# PAGE2.net
KiCad netlist of a schematic drawn in Altium Designer
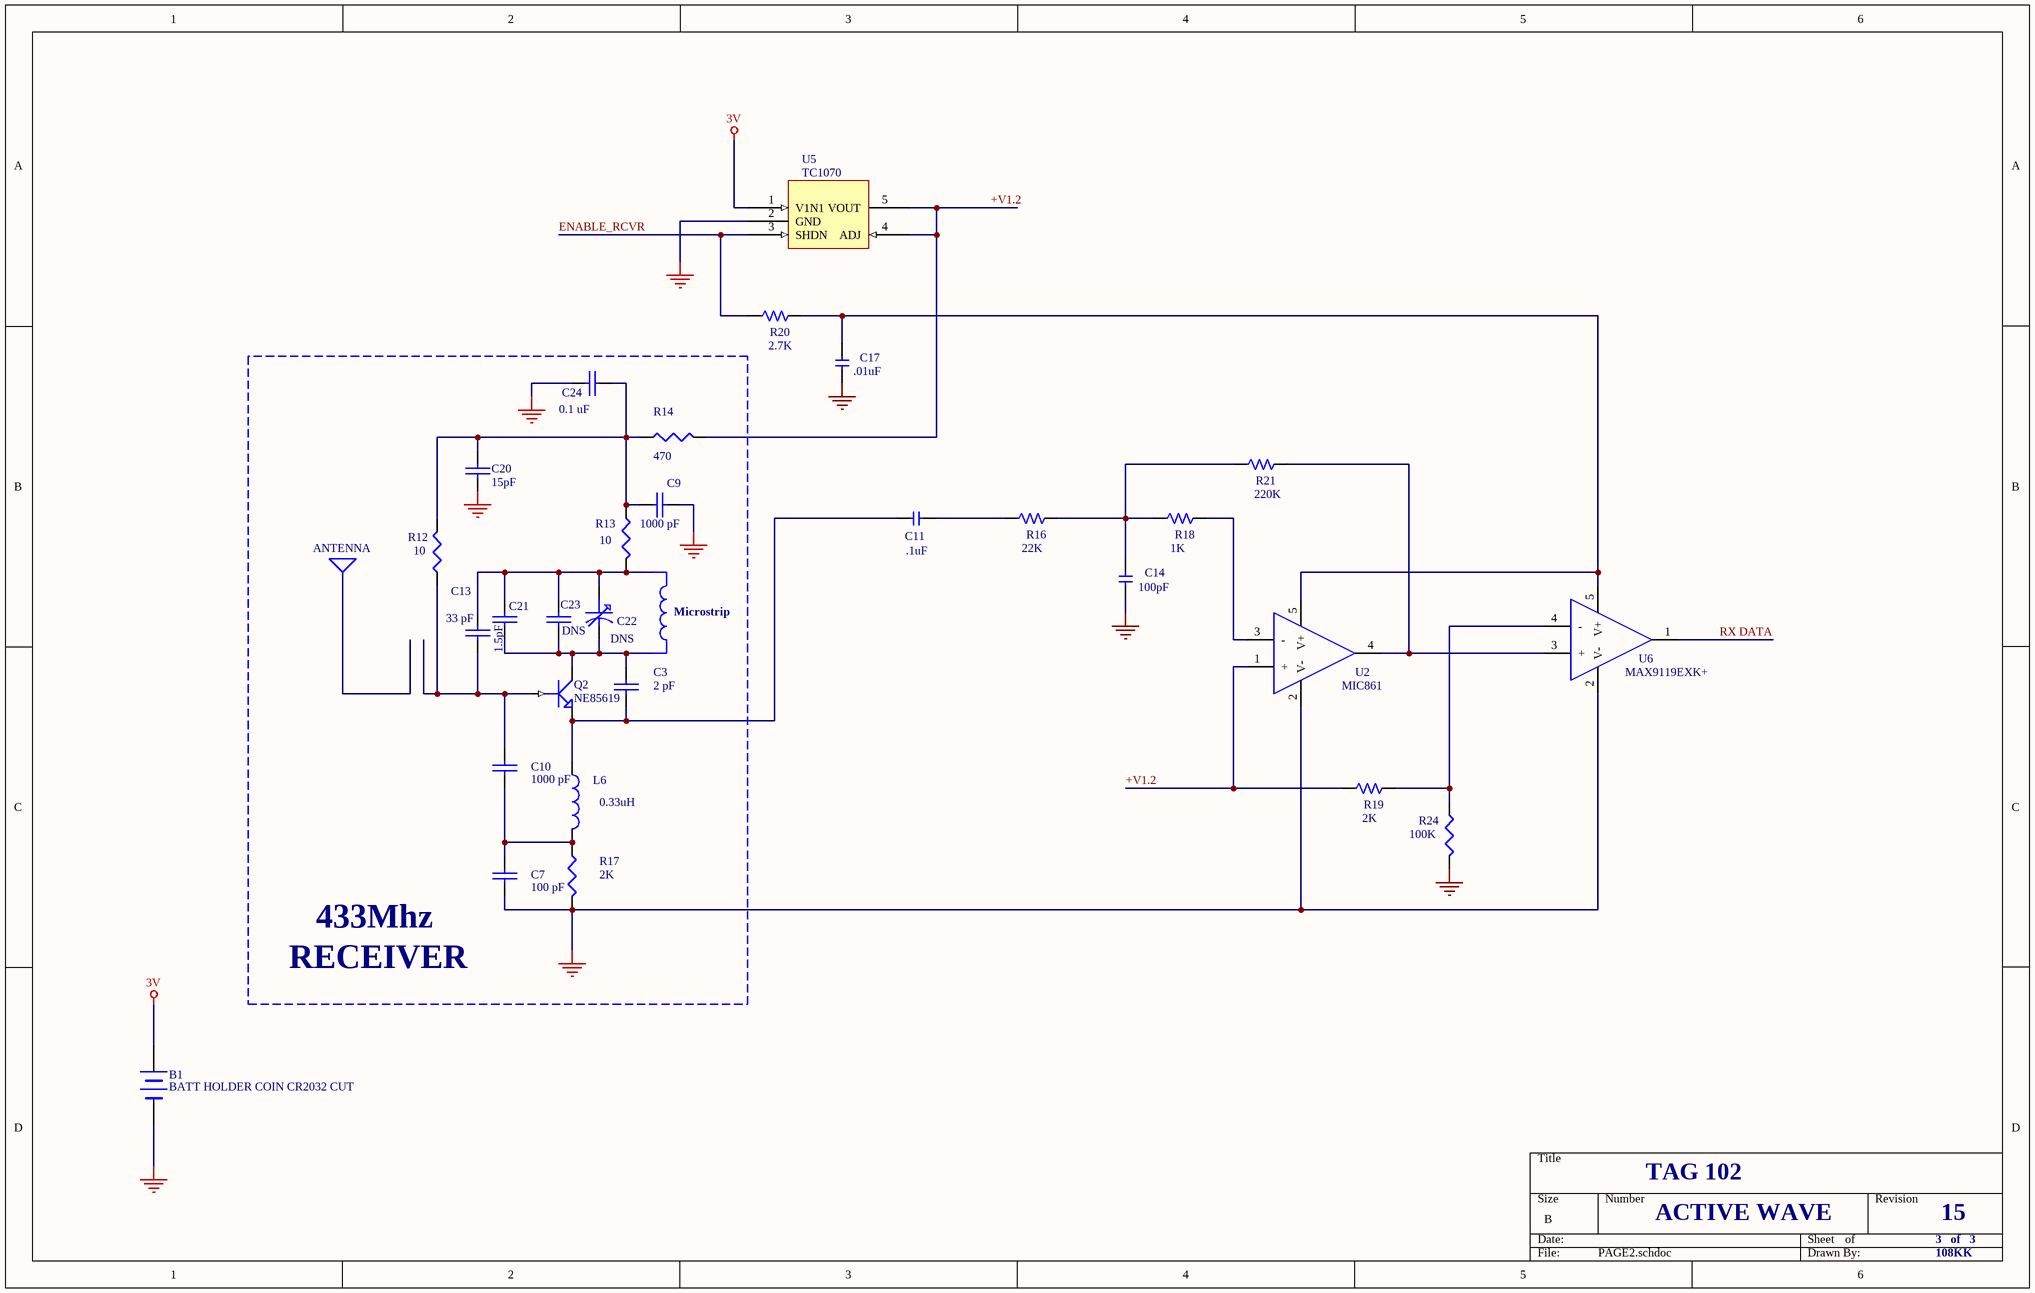
[diagram p0: PAGE2.schdoc]

(export (version "E")
  (design (tool "Eeschema 10.0.6"))
  (components
    (comp (ref "B1")
      (value "BATT HOLDER COIN CR2032 CUT")
      (footprint "BATT HOLDER1")
      (description "Battery")
      (libsource (lib "*") (part "BATTERY"))
    )
    (comp (ref "C3")
      (value "2 pF")
      (footprint "0603")
      (description "Capacitor")
      (libsource (lib "*") (part "CAP"))
    )
    (comp (ref "C7")
      (value "100 pF")
      (footprint "0603")
      (description "Capacitor")
      (libsource (lib "*") (part "CAP"))
    )
    (comp (ref "C9")
      (value "1000 pF")
      (footprint "0603")
      (description "Capacitor")
      (libsource (lib "*") (part "CAP"))
    )
    (comp (ref "C10")
      (value "1000 pF")
      (footprint "0603")
      (description "Capacitor")
      (libsource (lib "*") (part "CAP"))
    )
    (comp (ref "C11") (value ".1uF") (footprint "0603") (libsource (lib "*") (part "C")))
    (comp (ref "C13")
      (value "33 pF")
      (footprint "0603")
      (description "Capacitor")
      (libsource (lib "*") (part "CAP"))
    )
    (comp (ref "C14") (value "100pF") (footprint "0603") (libsource (lib "*") (part "C")))
    (comp (ref "C17") (value ".01uF") (footprint "0603") (libsource (lib "*") (part "C")))
    (comp (ref "C20")
      (value "15pF")
      (footprint "0603")
      (description "Capacitor")
      (libsource (lib "*") (part "CAP"))
    )
    (comp (ref "C21")
      (value "1.5pF")
      (footprint "0603")
      (description "Capacitor")
      (libsource (lib "*") (part "CAP"))
    )
    (comp (ref "C22") (value "DNS") (footprint "0603") (libsource (lib "*") (part "CAPACITOR VAR")))
    (comp (ref "C23")
      (value "DNS")
      (footprint "0603")
      (description "Capacitor")
      (libsource (lib "*") (part "CAP"))
    )
    (comp (ref "C24")
      (value "0.1 uF")
      (footprint "0603")
      (description "Capacitor")
      (libsource (lib "*") (part "CAP"))
    )
    (comp (ref "L6") (value "0.33uH") (footprint "0603") (libsource (lib "*") (part "INDUCTOR")))
    (comp (ref "Q2")
      (value "NE85619")
      (footprint "3 PIN ULTRA SUPER MINI MOLD")
      (description "NPN Transistor")
      (libsource (lib "*") (part "NPN1"))
    )
    (comp (ref "R12") (value "10") (footprint "0603") (libsource (lib "*") (part "R")))
    (comp (ref "R13") (value "10") (footprint "0603") (libsource (lib "*") (part "R")))
    (comp (ref "R14") (value "470") (footprint "0603") (libsource (lib "*") (part "R")))
    (comp (ref "R16") (value "22K") (footprint "0603") (libsource (lib "") (part "R_1")))
    (comp (ref "R17") (value "2K") (footprint "0603") (libsource (lib "*") (part "RESISTOR")))
    (comp (ref "R18") (value "1K") (footprint "0603") (libsource (lib "") (part "R_1")))
    (comp (ref "R19") (value "2K") (footprint "0603") (libsource (lib "") (part "R_1")))
    (comp (ref "R20") (value "2.7K") (footprint "0603") (libsource (lib "") (part "R_1")))
    (comp (ref "R21") (value "220K") (footprint "0603") (libsource (lib "") (part "R_1")))
    (comp (ref "R24") (value "100K") (footprint "0603") (libsource (lib "*") (part "R")))
    (comp (ref "U2") (value "MIC861") (libsource (lib "*") (part "OPAMP MIC861")))
    (comp (ref "U5") (value "TC1070") (footprint "SOT23-5A") (libsource (lib "*") (part "TC1070-2")))
    (comp (ref "U6")
      (value "MAX9119EXK+")
      (footprint "SC70")
      (libsource (lib "*") (part "COMPARATOR MAX9117"))
    )
  )
  (nets
    (net (code "1") (name "/+V1.2") (class "Default")
      (node (ref "R14") (pin "2") (pinfunction "2_2") (pintype "passive"))
      (node (ref "R19") (pin "1") (pinfunction "1_1") (pintype "passive"))
      (node (ref "U2") (pin "1") (pinfunction "+_1") (pintype "passive"))
      (node (ref "U5") (pin "4") (pinfunction "ADJ_4") (pintype "input"))
      (node (ref "U5") (pin "5") (pinfunction "VOUT_5") (pintype "power_in"))
    )
    (net (code "2") (name "/ENABLE_RCVR") (class "Default")
      (node (ref "R20") (pin "1") (pinfunction "1_1") (pintype "passive"))
      (node (ref "U5") (pin "3") (pinfunction "SHDN_3") (pintype "input"))
    )
    (net (code "3") (name "/RX DATA") (class "Default")
      (node (ref "U6") (pin "1") (pinfunction "OUT_1") (pintype "passive"))
    )
    (net (code "4") (name "3V") (class "Default")
      (node (ref "B1") (pin "2") (pinfunction "+_2") (pintype "passive"))
      (node (ref "U5") (pin "1") (pinfunction "V1N1_1") (pintype "input"))
    )
    (net (code "5") (name "GND") (class "Default")
      (node (ref "B1") (pin "1") (pinfunction "-_1") (pintype "passive"))
      (node (ref "C14") (pin "1") (pinfunction "1_1") (pintype "passive"))
      (node (ref "C17") (pin "1") (pinfunction "1_1") (pintype "passive"))
      (node (ref "C20") (pin "1") (pinfunction "1_1") (pintype "passive"))
      (node (ref "C24") (pin "1") (pinfunction "1_1") (pintype "passive"))
      (node (ref "C7") (pin "2") (pinfunction "2_2") (pintype "passive"))
      (node (ref "C9") (pin "2") (pinfunction "2_2") (pintype "passive"))
      (node (ref "R17") (pin "2") (pinfunction "2_2") (pintype "passive"))
      (node (ref "R24") (pin "2") (pinfunction "2_2") (pintype "passive"))
      (node (ref "U2") (pin "2") (pinfunction "V-_2") (pintype "passive"))
      (node (ref "U5") (pin "2") (pinfunction "GND_2") (pintype "power_in"))
      (node (ref "U6") (pin "2") (pinfunction "V-_2") (pintype "passive"))
    )
    (net (code "6") (name "Net-(C10-Pad1)") (class "Default")
      (node (ref "C10") (pin "1") (pinfunction "1_1") (pintype "passive"))
      (node (ref "C13") (pin "1") (pinfunction "1_1") (pintype "passive"))
      (node (ref "Q2") (pin "B") (pinfunction "B_B") (pintype "input"))
      (node (ref "R12") (pin "1") (pinfunction "1_1") (pintype "passive"))
    )
    (net (code "7") (name "Net-(C10-Pad2)") (class "Default")
      (node (ref "C10") (pin "2") (pinfunction "2_2") (pintype "passive"))
      (node (ref "C7") (pin "1") (pinfunction "1_1") (pintype "passive"))
      (node (ref "L6") (pin "2") (pinfunction "2_2") (pintype "passive"))
      (node (ref "R17") (pin "1") (pinfunction "1_1") (pintype "passive"))
    )
    (net (code "8") (name "Net-(C11-Pad1)") (class "Default")
      (node (ref "C11") (pin "1") (pinfunction "1_1") (pintype "passive"))
      (node (ref "C3") (pin "2") (pinfunction "2_2") (pintype "passive"))
      (node (ref "L6") (pin "1") (pinfunction "1_1") (pintype "passive"))
      (node (ref "Q2") (pin "E") (pinfunction "E_E") (pintype "passive"))
    )
    (net (code "9") (name "Net-(C11-Pad2)") (class "Default")
      (node (ref "C11") (pin "2") (pinfunction "2_2") (pintype "passive"))
      (node (ref "R16") (pin "1") (pinfunction "1_1") (pintype "passive"))
    )
    (net (code "10") (name "Net-(C13-Pad2)") (class "Default")
      (node (ref "C13") (pin "2") (pinfunction "2_2") (pintype "passive"))
      (node (ref "C21") (pin "1") (pinfunction "1_1") (pintype "passive"))
      (node (ref "C22") (pin "1") (pinfunction "1_1") (pintype "passive"))
      (node (ref "C23") (pin "1") (pinfunction "1_1") (pintype "passive"))
      (node (ref "R13") (pin "2") (pinfunction "2_2") (pintype "passive"))
    )
    (net (code "11") (name "Net-(C14-Pad2)") (class "Default")
      (node (ref "C14") (pin "2") (pinfunction "2_2") (pintype "passive"))
      (node (ref "R16") (pin "2") (pinfunction "2_2") (pintype "passive"))
      (node (ref "R18") (pin "1") (pinfunction "1_1") (pintype "passive"))
      (node (ref "R21") (pin "1") (pinfunction "1_1") (pintype "passive"))
    )
    (net (code "12") (name "Net-(C20-Pad2)") (class "Default")
      (node (ref "C20") (pin "2") (pinfunction "2_2") (pintype "passive"))
      (node (ref "C24") (pin "2") (pinfunction "2_2") (pintype "passive"))
      (node (ref "C9") (pin "1") (pinfunction "1_1") (pintype "passive"))
      (node (ref "R12") (pin "2") (pinfunction "2_2") (pintype "passive"))
      (node (ref "R13") (pin "1") (pinfunction "1_1") (pintype "passive"))
      (node (ref "R14") (pin "1") (pinfunction "1_1") (pintype "passive"))
    )
    (net (code "13") (name "Net-(C21-Pad2)") (class "Default")
      (node (ref "C21") (pin "2") (pinfunction "2_2") (pintype "passive"))
      (node (ref "C22") (pin "2") (pinfunction "2_2") (pintype "passive"))
      (node (ref "C23") (pin "2") (pinfunction "2_2") (pintype "passive"))
      (node (ref "C3") (pin "1") (pinfunction "1_1") (pintype "passive"))
      (node (ref "Q2") (pin "C") (pinfunction "C_C") (pintype "passive"))
    )
    (net (code "14") (name "Net-(U2--)") (class "Default")
      (node (ref "R18") (pin "2") (pinfunction "2_2") (pintype "passive"))
      (node (ref "U2") (pin "3") (pinfunction "-_3") (pintype "passive"))
    )
    (net (code "15") (name "Net-(U2-OUT)") (class "Default")
      (node (ref "R21") (pin "2") (pinfunction "2_2") (pintype "passive"))
      (node (ref "U2") (pin "4") (pinfunction "OUT_4") (pintype "passive"))
      (node (ref "U6") (pin "3") (pinfunction "+_3") (pintype "passive"))
    )
    (net (code "16") (name "Net-(U2-V+)") (class "Default")
      (node (ref "C17") (pin "2") (pinfunction "2_2") (pintype "passive"))
      (node (ref "R20") (pin "2") (pinfunction "2_2") (pintype "passive"))
      (node (ref "U2") (pin "5") (pinfunction "V+_5") (pintype "passive"))
      (node (ref "U6") (pin "5") (pinfunction "V+_5") (pintype "passive"))
    )
    (net (code "17") (name "Net-(U6--)") (class "Default")
      (node (ref "R19") (pin "2") (pinfunction "2_2") (pintype "passive"))
      (node (ref "R24") (pin "1") (pinfunction "1_1") (pintype "passive"))
      (node (ref "U6") (pin "4") (pinfunction "-_4") (pintype "passive"))
    )
  )
)
